# Main.net
KiCad netlist of a schematic drawn in Altium Designer
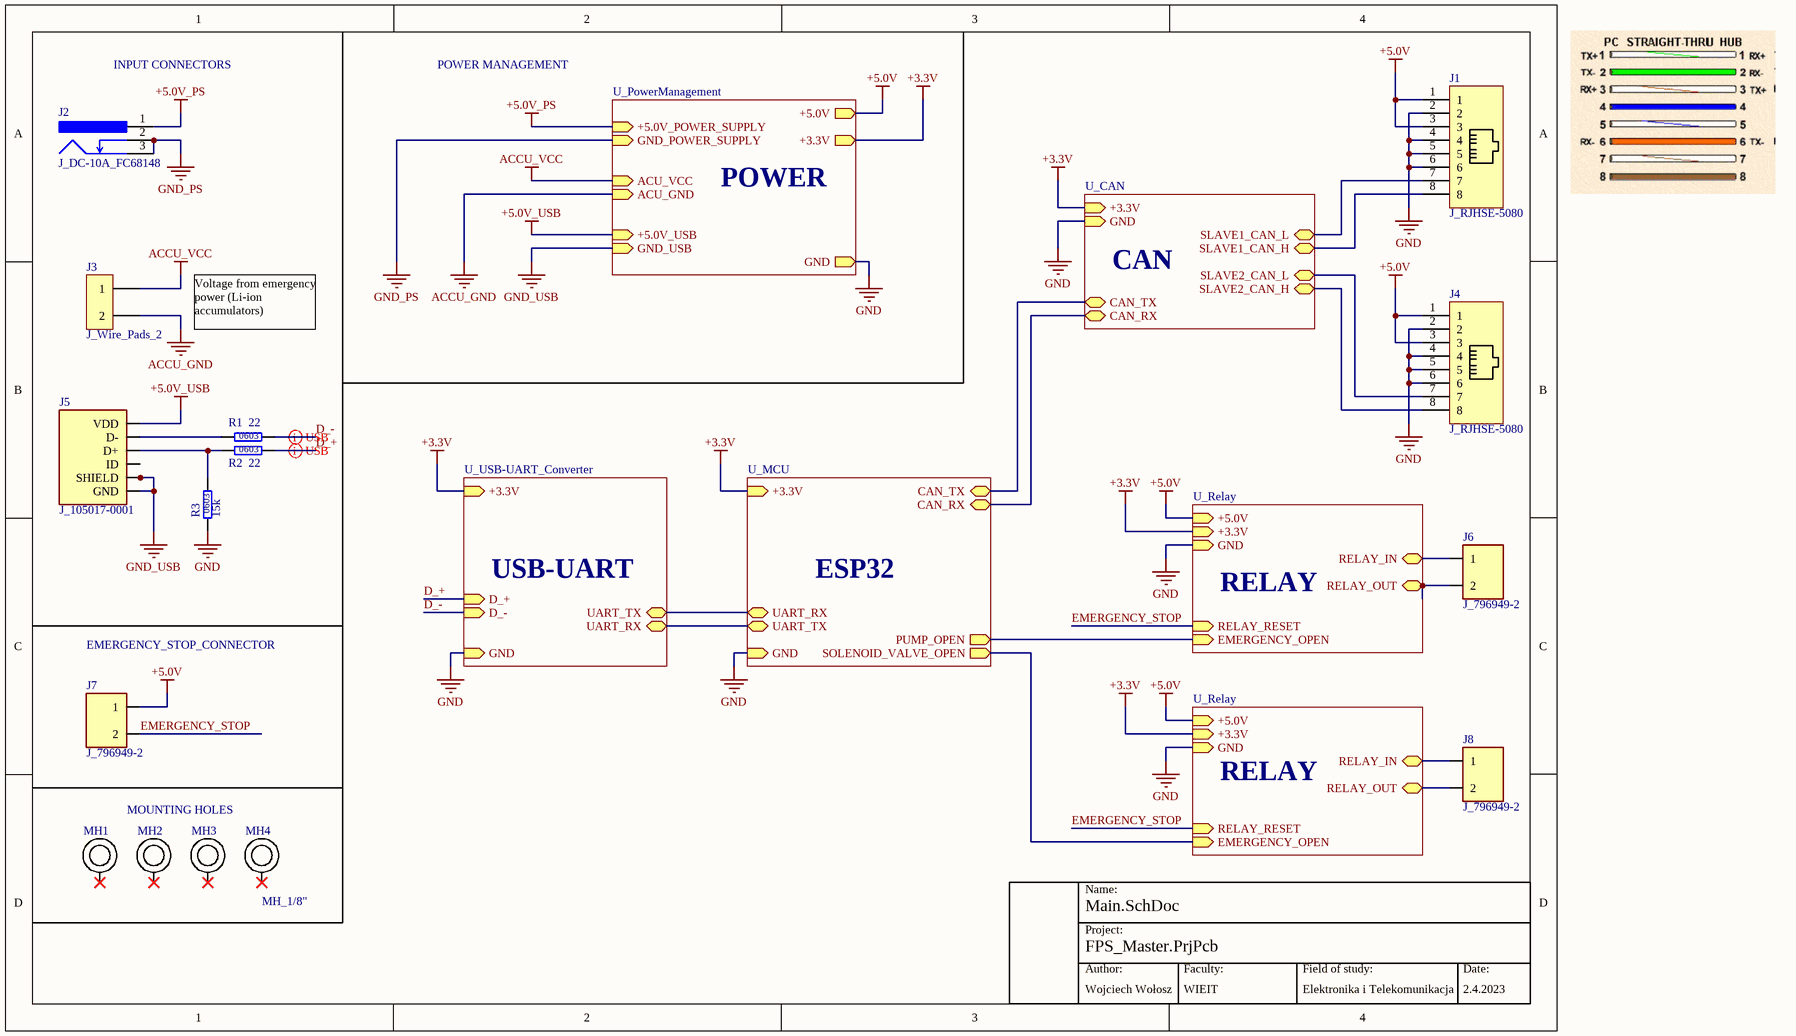
[diagram p0: Main.SchDoc]

(export (version "E")
  (design (tool "Eeschema 10.0.6"))
  (components
    (comp (ref "J1")
      (value "J_RJHSE-5080")
      (footprint "J_RJHSE-5080")
      (description "RJ-45; Jack Modular Connector 8p8c (RJ45, Ethernet) 90° Angle (Right) Unshielded")
      (libsource (lib "Altium Concord Pro on A365") (part "J_RJ-45_connector"))
    )
    (comp (ref "J2")
      (value "J_DC-10A_FC68148")
      (footprint "2_1x2_5_DC_CONN_THT")
      (description "Socket; DC supply; male; 5.5/2.1mm; 5.5mm; 2.1mm; soldering; 5A THT")
      (fields (field (name "MANUF. PART") "DC-10A FC68148"))
      (libsource (lib "Altium Concord Pro on A365") (part "P_DC-JACK"))
    )
    (comp (ref "J3")
      (value "J_Wire_Pads_2")
      (footprint "J_Wire_Pads_2")
      (description "Pads used for soldering wires / measurement,")
      (libsource (lib "Altium Concord Pro on A365") (part "J_Wire_Pads_2"))
    )
    (comp (ref "J4")
      (value "J_RJHSE-5080")
      (footprint "J_RJHSE-5080")
      (description "RJ-45; Jack Modular Connector 8p8c (RJ45, Ethernet) 90° Angle (Right) Unshielded")
      (libsource (lib "Altium Concord Pro on A365") (part "J_RJ-45_connector"))
    )
    (comp (ref "J5")
      (value "J_105017-0001")
      (footprint "MICROUSB_THT")
      (description "USB Connectors MICRO USB B RECPT BTTM MNT SMT TH TABS")
      (libsource (lib "Altium Concord Pro on A365") (part "J_105017-0001"))
    )
    (comp (ref "J6")
      (value "J_796949-2")
      (footprint "TERMINAL_BLOCK_5.08_2POS")
      (description "Fixed Terminal Blocks 5.08MM VERTICAL 2P wire protector")
      (libsource (lib "Altium Concord Pro on A365") (part "J_796949-2-Symbol-1"))
    )
    (comp (ref "J7")
      (value "J_796949-2")
      (footprint "TERMINAL_BLOCK_5.08_2POS")
      (description "Fixed Terminal Blocks 5.08MM VERTICAL 2P wire protector")
      (libsource (lib "") (part "J_796949-2-Symbol-1_1"))
    )
    (comp (ref "J8")
      (value "J_796949-2")
      (footprint "TERMINAL_BLOCK_5.08_2POS")
      (description "Fixed Terminal Blocks 5.08MM VERTICAL 2P wire protector")
      (libsource (lib "Altium Concord Pro on A365") (part "J_796949-2-Symbol-1"))
    )
    (comp (ref "MH1")
      (value "MH_1/8\"")
      (footprint "MH_1_8\"")
      (description "1/8\"/0.22\" (3.2mm x 5.5mm) Mounting hole")
      (libsource (lib "Altium Concord Pro on A365") (part "MH_1_8{dblquote}-Symbol-1"))
    )
    (comp (ref "MH2")
      (value "MH_1/8\"")
      (footprint "MH_1_8\"")
      (description "1/8\"/0.22\" (3.2mm x 5.5mm) Mounting hole")
      (libsource (lib "Altium Concord Pro on A365") (part "MH_1_8{dblquote}-Symbol-1"))
    )
    (comp (ref "MH3")
      (value "MH_1/8\"")
      (footprint "MH_1_8\"")
      (description "1/8\"/0.22\" (3.2mm x 5.5mm) Mounting hole")
      (libsource (lib "Altium Concord Pro on A365") (part "MH_1_8{dblquote}-Symbol-1"))
    )
    (comp (ref "MH4")
      (value "MH_1/8\"")
      (footprint "MH_1_8\"")
      (description "1/8\"/0.22\" (3.2mm x 5.5mm) Mounting hole")
      (libsource (lib "Altium Concord Pro on A365") (part "MH_1_8{dblquote}-Symbol-1"))
    )
    (comp (ref "R1")
      (value "22")
      (footprint "R_0603")
      (description "R_22_0603_5")
      (fields (field (name "SCH_FOOTPRINT") "0603") (field (name "TOLERANCE") "5%"))
      (libsource (lib "Altium Concord Pro on A365") (part "R"))
    )
    (comp (ref "R2")
      (value "22")
      (footprint "R_0603")
      (description "R_22_0603_5")
      (fields (field (name "SCH_FOOTPRINT") "0603") (field (name "TOLERANCE") "5%"))
      (libsource (lib "Altium Concord Pro on A365") (part "R"))
    )
    (comp (ref "R3")
      (value "15k")
      (footprint "R_0603")
      (description "Thick Film Resistors - SMD 1/10watt 15Kohms 5%")
      (fields
        (field (name "SCH_FOOTPRINT") "0603")
        (field (name "TOLERANCE") "5%")
        (field (name "Comment") "R_15k_0603_5")
      )
      (libsource (lib "Altium Concord Pro on A365") (part "R"))
    )
  )
  (nets
    (net (code "2") (name "+5.0V") (class "Default")
      (node (ref "J1") (pin "1") (pinfunction "1_1") (pintype "passive"))
      (node (ref "J1") (pin "3") (pinfunction "3_3") (pintype "passive"))
      (node (ref "J4") (pin "1") (pinfunction "1_1") (pintype "passive"))
      (node (ref "J4") (pin "3") (pinfunction "3_3") (pintype "passive"))
      (node (ref "J7") (pin "1") (pinfunction "1_1") (pintype "passive"))
    )
    (net (code "3") (name "+5.0V_PS") (class "Default")
      (node (ref "J2") (pin "1") (pinfunction "1_1") (pintype "passive"))
    )
    (net (code "4") (name "+5.0V_USB") (class "Default")
      (node (ref "J5") (pin "1") (pinfunction "VDD_1") (pintype "power_in"))
    )
    (net (code "8") (name "/D_+") (class "Default")
      (node (ref "R2") (pin "2") (pinfunction "2_2") (pintype "passive"))
    )
    (net (code "9") (name "/D_-") (class "Default")
      (node (ref "R1") (pin "2") (pinfunction "2_2") (pintype "passive"))
    )
    (net (code "10") (name "/EMERGENCY_STOP") (class "Default")
      (node (ref "J7") (pin "2") (pinfunction "2_2") (pintype "passive"))
    )
    (net (code "12") (name "/RELAY_IN") (class "Default")
      (node (ref "J8") (pin "1") (pinfunction "1_1") (pintype "passive"))
    )
    (net (code "13") (name "/RELAY_IN_1") (class "Default")
      (node (ref "J6") (pin "1") (pinfunction "1_1") (pintype "passive"))
    )
    (net (code "14") (name "/RELAY_OUT") (class "Default")
      (node (ref "J8") (pin "2") (pinfunction "2_2") (pintype "passive"))
    )
    (net (code "15") (name "/RELAY_OUT_1") (class "Default")
      (node (ref "J6") (pin "2") (pinfunction "2_2") (pintype "passive"))
    )
    (net (code "16") (name "/SLAVE1_CAN_H") (class "Default")
      (node (ref "J1") (pin "8") (pinfunction "8_8") (pintype "passive"))
    )
    (net (code "17") (name "/SLAVE1_CAN_L") (class "Default")
      (node (ref "J1") (pin "7") (pinfunction "7_7") (pintype "passive"))
    )
    (net (code "18") (name "/SLAVE2_CAN_H") (class "Default")
      (node (ref "J4") (pin "8") (pinfunction "8_8") (pintype "passive"))
    )
    (net (code "19") (name "/SLAVE2_CAN_L") (class "Default")
      (node (ref "J4") (pin "7") (pinfunction "7_7") (pintype "passive"))
    )
    (net (code "23") (name "ACCU_GND") (class "Default")
      (node (ref "J3") (pin "2") (pinfunction "2_2") (pintype "passive"))
    )
    (net (code "24") (name "ACCU_VCC") (class "Default")
      (node (ref "J3") (pin "1") (pinfunction "1_1") (pintype "passive"))
    )
    (net (code "25") (name "GND") (class "Default")
      (node (ref "J1") (pin "2") (pinfunction "2_2") (pintype "passive"))
      (node (ref "J1") (pin "4") (pinfunction "4_4") (pintype "passive"))
      (node (ref "J1") (pin "5") (pinfunction "5_5") (pintype "passive"))
      (node (ref "J1") (pin "6") (pinfunction "6_6") (pintype "passive"))
      (node (ref "J4") (pin "2") (pinfunction "2_2") (pintype "passive"))
      (node (ref "J4") (pin "4") (pinfunction "4_4") (pintype "passive"))
      (node (ref "J4") (pin "5") (pinfunction "5_5") (pintype "passive"))
      (node (ref "J4") (pin "6") (pinfunction "6_6") (pintype "passive"))
      (node (ref "R3") (pin "1") (pinfunction "1_1") (pintype "passive"))
    )
    (net (code "26") (name "GND_PS") (class "Default")
      (node (ref "J2") (pin "2") (pinfunction "2_2") (pintype "passive"))
      (node (ref "J2") (pin "3") (pinfunction "4_3") (pintype "passive"))
    )
    (net (code "27") (name "GND_USB") (class "Default")
      (node (ref "J5") (pin "5") (pinfunction "GND_5") (pintype "power_in"))
      (node (ref "J5") (pin "P$10") (pinfunction "SHIELD_P$10") (pintype "passive"))
      (node (ref "J5") (pin "P$11") (pinfunction "SHIELD_P$11") (pintype "passive"))
      (node (ref "J5") (pin "P$8") (pinfunction "SHIELD_P$8") (pintype "passive"))
      (node (ref "J5") (pin "P$9") (pinfunction "SHIELD_P$9") (pintype "passive"))
    )
    (net (code "28") (name "Net-(J5-D+)") (class "Default")
      (node (ref "J5") (pin "3") (pinfunction "D+_3") (pintype "bidirectional"))
      (node (ref "R2") (pin "1") (pinfunction "1_1") (pintype "passive"))
      (node (ref "R3") (pin "2") (pinfunction "2_2") (pintype "passive"))
    )
    (net (code "29") (name "Net-(J5-D-)") (class "Default")
      (node (ref "J5") (pin "2") (pinfunction "D-_2") (pintype "bidirectional"))
      (node (ref "R1") (pin "1") (pinfunction "1_1") (pintype "passive"))
    )
    (net (code "30") (name "unconnected-(J5-ID-Pad4)") (class "Default")
      (node (ref "J5") (pin "4") (pinfunction "ID_4") (pintype "passive"))
    )
    (net (code "31") (name "unconnected-(MH1-Pad1)") (class "Default")
      (node (ref "MH1") (pin "1") (pinfunction "1_1") (pintype "passive+no_connect"))
    )
    (net (code "32") (name "unconnected-(MH2-Pad1)") (class "Default")
      (node (ref "MH2") (pin "1") (pinfunction "1_1") (pintype "passive+no_connect"))
    )
    (net (code "33") (name "unconnected-(MH3-Pad1)") (class "Default")
      (node (ref "MH3") (pin "1") (pinfunction "1_1") (pintype "passive+no_connect"))
    )
    (net (code "34") (name "unconnected-(MH4-Pad1)") (class "Default")
      (node (ref "MH4") (pin "1") (pinfunction "1_1") (pintype "passive+no_connect"))
    )
  )
)
